# filter-1.net
KiCad netlist of a schematic drawn in Altium Designer
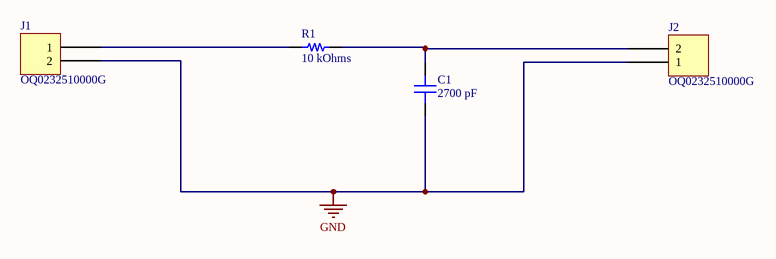
[diagram p0: filter-1.SchDoc]

(export (version "E")
  (design (tool "Eeschema 10.0.6"))
  (components
    (comp (ref "C1")
      (value "2700 pF")
      (footprint "CAP 0603_1608")
      (description "CAP CER 2700PF 25V NP0 0603")
      (fields (field (name "PART NUMBER") "C0603C272F3GAC7867") (field (name "MANUFACTURER") "KEMET"))
      (libsource (lib "Celestial Altium Library - altium_library") (part "Capacitor"))
    )
    (comp (ref "J1")
      (value "OQ0232510000G")
      (footprint "FCI 06-381-2PIN")
      (description "TERM BLOCK HDR 2POS 90DEG 3.81MM")
      (fields (field (name "MANUFACTURER") "Amphenol Anytek"))
      (libsource (lib "") (part "2 Pin_1"))
    )
    (comp (ref "J2")
      (value "OQ0232510000G")
      (footprint "FCI 06-381-2PIN")
      (description "TERM BLOCK HDR 2POS 90DEG 3.81MM")
      (fields (field (name "MANUFACTURER") "Amphenol Anytek"))
      (libsource (lib "Celestial Altium Library - altium_library") (part "2 Pin"))
    )
    (comp (ref "R1")
      (value "10 kOhms")
      (footprint "RES 0603_1608")
      (description "RES 10K OHM 0.1% 1/16W 0603")
      (fields
        (field (name "PART NUMBER") "RNCS0603BKE10K0")
        (field (name "MANUFACTURER") "Stackpole Electronics Inc")
      )
      (libsource (lib "Celestial Altium Library - altium_library") (part "Resistor"))
    )
  )
  (nets
    (net (code "1") (name "GND") (class "Default")
      (node (ref "C1") (pin "1") (pinfunction "1_1") (pintype "passive"))
      (node (ref "J1") (pin "2") (pinfunction "2_2") (pintype "passive"))
      (node (ref "J2") (pin "1") (pinfunction "1_1") (pintype "passive"))
    )
    (net (code "2") (name "Net-(C1-Pad2)") (class "Default")
      (node (ref "C1") (pin "2") (pinfunction "2_2") (pintype "passive"))
      (node (ref "J2") (pin "2") (pinfunction "2_2") (pintype "passive"))
      (node (ref "R1") (pin "2") (pinfunction "2_2") (pintype "passive"))
    )
    (net (code "3") (name "Net-(J1-Pad1)") (class "Default")
      (node (ref "J1") (pin "1") (pinfunction "1_1") (pintype "passive"))
      (node (ref "R1") (pin "1") (pinfunction "1_1") (pintype "passive"))
    )
  )
)
